# SMART_FARM.net
KiCad netlist of a schematic drawn in Altium Designer
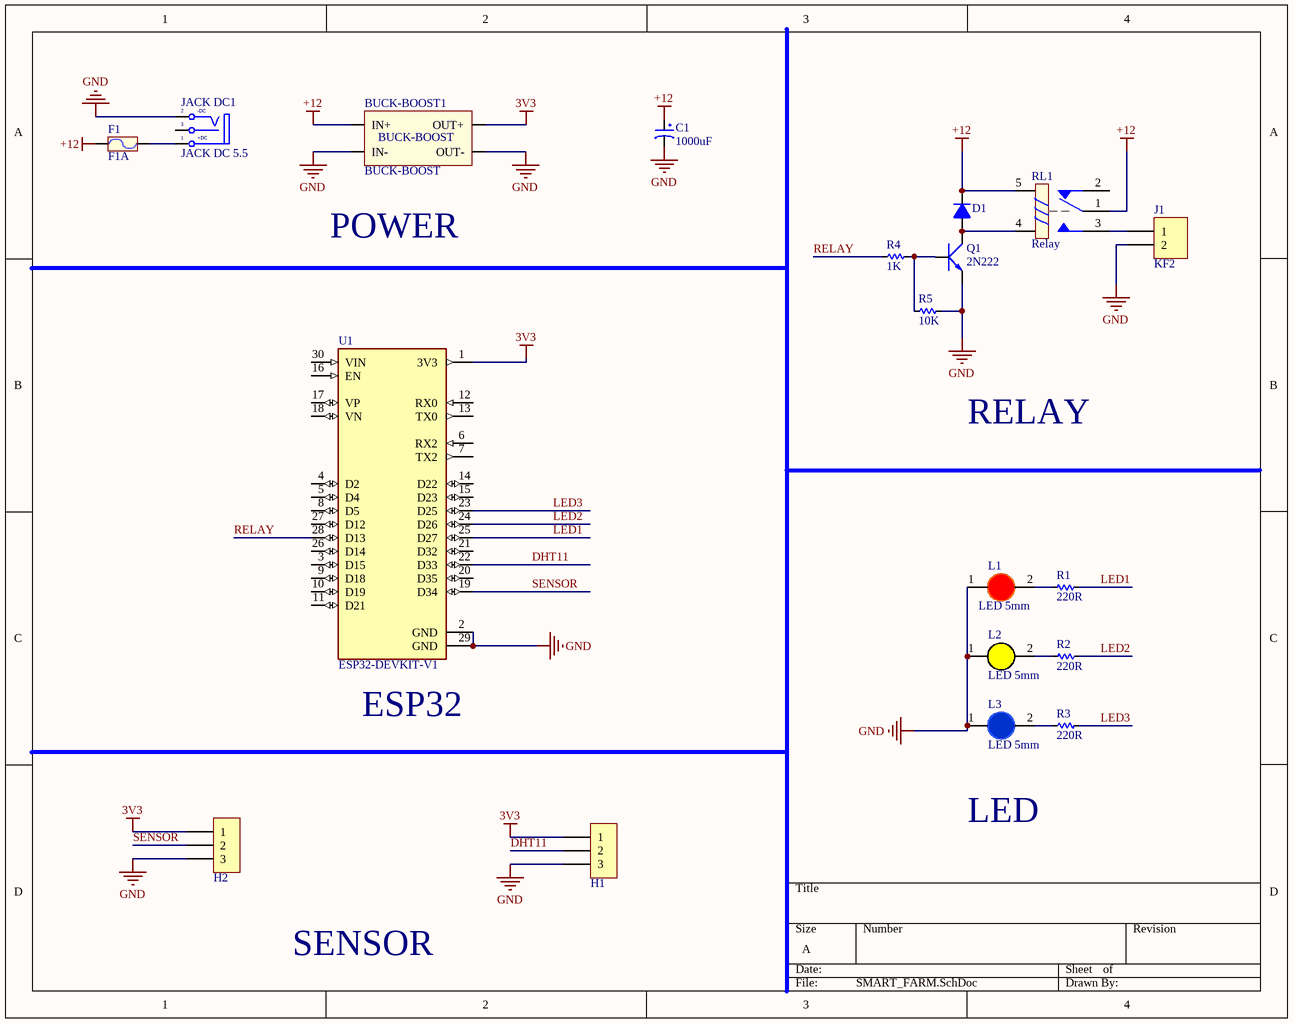
[diagram p0: SMART_FARM.SchDoc]

(export (version "E")
  (design (tool "Eeschema 10.0.6"))
  (components
    (comp (ref "BUCK-BOOST1")
      (value "BUCK-BOOST")
      (footprint "BUCK3A")
      (libsource (lib "Thu Vien Chuan") (part "BUCK-BOOST"))
    )
    (comp (ref "C1")
      (value "1000uF")
      (footprint "tu hoa 13mm")
      (description "Cắm")
      (libsource (lib "Altium_Lib_by_KhueNguyenCreator") (part "Tu Hoa 1000uF 25V 13x21"))
    )
    (comp (ref "D1")
      (value "100v")
      (footprint "DIODE 1A")
      (description "Cắm")
      (libsource (lib "Altium_Lib_by_KhueNguyenCreator") (part "Diode 1N4007"))
    )
    (comp (ref "F1")
      (value "F1A")
      (footprint "FUSE2")
      (description "Fuse")
      (fields (field (name "DESIGNED BY") "VanDungEvn"))
      (libsource (lib "LIBRARY") (part "Fuse"))
    )
    (comp (ref "H1")
      (value "Header 3P 2.54 Duc Thang")
      (footprint "XH2.54M-3")
      (description "Cắm")
      (libsource (lib "Altium_Lib_by_KhueNguyenCreator") (part "Header 3P 2.54 Duc Thang"))
    )
    (comp (ref "H2")
      (value "Header 3P 2.54 Duc Thang")
      (footprint "XH2.54M-3")
      (description "Cắm")
      (libsource (lib "Altium_Lib_by_KhueNguyenCreator") (part "Header 3P 2.54 Duc Thang"))
    )
    (comp (ref "J1")
      (value "KF2")
      (footprint "KF2-5.08")
      (fields
        (field (name "MANUFACTURER") "Würth Elektronik eiSos GmbH")
        (field (name "PARTNO") "691103110002")
        (field (name "CREATED BY") "Karrer Zheng")
      )
      (libsource (lib "Thu Vien Chuan") (part "KF2"))
    )
    (comp (ref "JACK DC1")
      (value "JACK DC 5.5")
      (footprint "JACK DC 5.5")
      (libsource (lib "Altium_Lib_by_KhueNguyenCreator") (part "JACK DC 5.5"))
    )
    (comp (ref "L1")
      (value "LED 5mm")
      (footprint "LED-5MM-RED")
      (description "Cắm")
      (libsource (lib "Altium_Lib_by_KhueNguyenCreator") (part "LED 5mm Do"))
    )
    (comp (ref "L2")
      (value "LED 5mm")
      (footprint "LED-5MM-Yellow")
      (description "Cắm")
      (libsource (lib "Altium_Lib_by_KhueNguyenCreator") (part "LED 5mm Vang"))
    )
    (comp (ref "L3")
      (value "LED 5mm")
      (footprint "LED-5MM-BLUE")
      (description "Cắm")
      (libsource (lib "Altium_Lib_by_KhueNguyenCreator") (part "LED 5mm Xanh Duong"))
    )
    (comp (ref "Q1")
      (value "2N222")
      (footprint "TO92-123")
      (description "NPN 600mW, ECB")
      (libsource (lib "LIBRARY") (part "2N222"))
    )
    (comp (ref "R1")
      (value "220R")
      (footprint "RES-1/4W")
      (description "Res")
      (fields
        (field (name "MANUFACTURER") "Generic Components")
        (field (name "PUBLISHER") "Altium Hobart Technology Centre")
      )
      (libsource (lib "LIBRARY") (part "Res"))
    )
    (comp (ref "R2")
      (value "220R")
      (footprint "RES-1/4W")
      (description "Res")
      (fields
        (field (name "MANUFACTURER") "Generic Components")
        (field (name "PUBLISHER") "Altium Hobart Technology Centre")
      )
      (libsource (lib "LIBRARY") (part "Res"))
    )
    (comp (ref "R3")
      (value "220R")
      (footprint "RES-1/4W")
      (description "Res")
      (fields
        (field (name "MANUFACTURER") "Generic Components")
        (field (name "PUBLISHER") "Altium Hobart Technology Centre")
      )
      (libsource (lib "LIBRARY") (part "Res"))
    )
    (comp (ref "R4")
      (value "1K")
      (footprint "RES-1/4W")
      (description "Res")
      (fields
        (field (name "MANUFACTURER") "Generic Components")
        (field (name "PUBLISHER") "Altium Hobart Technology Centre")
      )
      (libsource (lib "LIBRARY") (part "Res"))
    )
    (comp (ref "R5")
      (value "10K")
      (footprint "RES-1/4W")
      (description "Res")
      (fields
        (field (name "MANUFACTURER") "Generic Components")
        (field (name "PUBLISHER") "Altium Hobart Technology Centre")
      )
      (libsource (lib "LIBRARY") (part "Res"))
    )
    (comp (ref "RL1")
      (value "Relay")
      (footprint "Relay 5 Chan SRD")
      (description "Relay 5 Chan")
      (libsource (lib "Altium_Lib_by_KhueNguyenCreator") (part "Relay 5 Chan SRD"))
    )
    (comp (ref "U1")
      (value "ESP32-DEVKIT-V1")
      (footprint "MODULE_ESP32_DEVKIT_V1")
      (fields (field (name "MF") "Do it"))
      (libsource (lib "ESP32-DEVKIT-V1") (part "ESP32-DEVKIT-V1"))
    )
  )
  (nets
    (net (code "1") (name "+12") (class "Default")
      (node (ref "BUCK-BOOST1") (pin "1") (pinfunction "IN+_1") (pintype "passive"))
      (node (ref "C1") (pin "1") (pinfunction "1_1") (pintype "passive"))
      (node (ref "D1") (pin "2") (pinfunction "K_2") (pintype "passive"))
      (node (ref "F1") (pin "1") (pinfunction "1_1") (pintype "passive"))
      (node (ref "RL1") (pin "1") (pinfunction "1_1") (pintype "passive"))
      (node (ref "RL1") (pin "5") (pinfunction "5_5") (pintype "passive"))
    )
    (net (code "2") (name "/DHT11") (class "Default")
      (node (ref "H1") (pin "2") (pinfunction "2_2") (pintype "passive"))
      (node (ref "U1") (pin "22") (pinfunction "D33_22") (pintype "bidirectional"))
    )
    (net (code "3") (name "/LED1") (class "Default")
      (node (ref "R1") (pin "1") (pinfunction "1_1") (pintype "passive"))
      (node (ref "U1") (pin "25") (pinfunction "D27_25") (pintype "bidirectional"))
    )
    (net (code "4") (name "/LED2") (class "Default")
      (node (ref "R2") (pin "1") (pinfunction "1_1") (pintype "passive"))
      (node (ref "U1") (pin "24") (pinfunction "D26_24") (pintype "bidirectional"))
    )
    (net (code "5") (name "/LED3") (class "Default")
      (node (ref "R3") (pin "1") (pinfunction "1_1") (pintype "passive"))
      (node (ref "U1") (pin "23") (pinfunction "D25_23") (pintype "bidirectional"))
    )
    (net (code "6") (name "/RELAY") (class "Default")
      (node (ref "R4") (pin "2") (pinfunction "2_2") (pintype "passive"))
      (node (ref "U1") (pin "28") (pinfunction "D13_28") (pintype "bidirectional"))
    )
    (net (code "7") (name "/SENSOR") (class "Default")
      (node (ref "H2") (pin "2") (pinfunction "2_2") (pintype "passive"))
      (node (ref "U1") (pin "19") (pinfunction "D34_19") (pintype "bidirectional"))
    )
    (net (code "8") (name "3V3") (class "Default")
      (node (ref "BUCK-BOOST1") (pin "4") (pinfunction "OUT+_4") (pintype "passive"))
      (node (ref "H1") (pin "1") (pinfunction "1_1") (pintype "passive"))
      (node (ref "H2") (pin "1") (pinfunction "1_1") (pintype "passive"))
      (node (ref "U1") (pin "1") (pinfunction "3V3_1") (pintype "output"))
    )
    (net (code "9") (name "GND") (class "Default")
      (node (ref "BUCK-BOOST1") (pin "2") (pinfunction "IN-_2") (pintype "passive"))
      (node (ref "BUCK-BOOST1") (pin "3") (pinfunction "OUT-_3") (pintype "passive"))
      (node (ref "C1") (pin "2") (pinfunction "2_2") (pintype "passive"))
      (node (ref "H1") (pin "3") (pinfunction "3_3") (pintype "passive"))
      (node (ref "H2") (pin "3") (pinfunction "3_3") (pintype "passive"))
      (node (ref "J1") (pin "2") (pinfunction "2_2") (pintype "passive"))
      (node (ref "JACK DC1") (pin "2") (pinfunction "TN_2") (pintype "passive"))
      (node (ref "L1") (pin "1") (pinfunction "A_1") (pintype "passive"))
      (node (ref "L2") (pin "1") (pinfunction "A_1") (pintype "passive"))
      (node (ref "L3") (pin "1") (pinfunction "A_1") (pintype "passive"))
      (node (ref "Q1") (pin "1") (pinfunction "E_1") (pintype "passive"))
      (node (ref "R5") (pin "1") (pinfunction "1_1") (pintype "passive"))
      (node (ref "U1") (pin "2") (pinfunction "GND_2") (pintype "power_in"))
      (node (ref "U1") (pin "29") (pinfunction "GND_29") (pintype "power_in"))
    )
    (net (code "10") (name "Net-(D1-A)") (class "Default")
      (node (ref "D1") (pin "1") (pinfunction "A_1") (pintype "passive"))
      (node (ref "Q1") (pin "3") (pinfunction "C_3") (pintype "passive"))
      (node (ref "RL1") (pin "4") (pinfunction "4_4") (pintype "passive"))
    )
    (net (code "11") (name "Net-(J1-Pad1)") (class "Default")
      (node (ref "J1") (pin "1") (pinfunction "1_1") (pintype "passive"))
      (node (ref "RL1") (pin "3") (pinfunction "3_3") (pintype "passive"))
    )
    (net (code "12") (name "Net-(JACK DC1-T)") (class "Default")
      (node (ref "F1") (pin "2") (pinfunction "2_2") (pintype "passive"))
      (node (ref "JACK DC1") (pin "1") (pinfunction "T_1") (pintype "passive"))
    )
    (net (code "13") (name "Net-(L1-K)") (class "Default")
      (node (ref "L1") (pin "2") (pinfunction "K_2") (pintype "passive"))
      (node (ref "R1") (pin "2") (pinfunction "2_2") (pintype "passive"))
    )
    (net (code "14") (name "Net-(L2-K)") (class "Default")
      (node (ref "L2") (pin "2") (pinfunction "K_2") (pintype "passive"))
      (node (ref "R2") (pin "2") (pinfunction "2_2") (pintype "passive"))
    )
    (net (code "15") (name "Net-(L3-K)") (class "Default")
      (node (ref "L3") (pin "2") (pinfunction "K_2") (pintype "passive"))
      (node (ref "R3") (pin "2") (pinfunction "2_2") (pintype "passive"))
    )
    (net (code "16") (name "Net-(Q1-B)") (class "Default")
      (node (ref "Q1") (pin "2") (pinfunction "B_2") (pintype "passive"))
      (node (ref "R4") (pin "1") (pinfunction "1_1") (pintype "passive"))
      (node (ref "R5") (pin "2") (pinfunction "2_2") (pintype "passive"))
    )
    (net (code "17") (name "unconnected-(JACK DC1-S-Pad3)") (class "Default")
      (node (ref "JACK DC1") (pin "3") (pinfunction "S_3") (pintype "power_in"))
    )
    (net (code "18") (name "unconnected-(RL1-Pad2)") (class "Default")
      (node (ref "RL1") (pin "2") (pinfunction "2_2") (pintype "passive"))
    )
    (net (code "19") (name "unconnected-(U1-D2-Pad4)") (class "Default")
      (node (ref "U1") (pin "4") (pinfunction "D2_4") (pintype "bidirectional"))
    )
    (net (code "20") (name "unconnected-(U1-D4-Pad5)") (class "Default")
      (node (ref "U1") (pin "5") (pinfunction "D4_5") (pintype "bidirectional"))
    )
    (net (code "21") (name "unconnected-(U1-D5-Pad8)") (class "Default")
      (node (ref "U1") (pin "8") (pinfunction "D5_8") (pintype "bidirectional"))
    )
    (net (code "22") (name "unconnected-(U1-D12-Pad27)") (class "Default")
      (node (ref "U1") (pin "27") (pinfunction "D12_27") (pintype "bidirectional"))
    )
    (net (code "23") (name "unconnected-(U1-D14-Pad26)") (class "Default")
      (node (ref "U1") (pin "26") (pinfunction "D14_26") (pintype "bidirectional"))
    )
    (net (code "24") (name "unconnected-(U1-D15-Pad3)") (class "Default")
      (node (ref "U1") (pin "3") (pinfunction "D15_3") (pintype "bidirectional"))
    )
    (net (code "25") (name "unconnected-(U1-D18-Pad9)") (class "Default")
      (node (ref "U1") (pin "9") (pinfunction "D18_9") (pintype "bidirectional"))
    )
    (net (code "26") (name "unconnected-(U1-D19-Pad10)") (class "Default")
      (node (ref "U1") (pin "10") (pinfunction "D19_10") (pintype "bidirectional"))
    )
    (net (code "27") (name "unconnected-(U1-D21-Pad11)") (class "Default")
      (node (ref "U1") (pin "11") (pinfunction "D21_11") (pintype "bidirectional"))
    )
    (net (code "28") (name "unconnected-(U1-D22-Pad14)") (class "Default")
      (node (ref "U1") (pin "14") (pinfunction "D22_14") (pintype "bidirectional"))
    )
    (net (code "29") (name "unconnected-(U1-D23-Pad15)") (class "Default")
      (node (ref "U1") (pin "15") (pinfunction "D23_15") (pintype "bidirectional"))
    )
    (net (code "30") (name "unconnected-(U1-D32-Pad21)") (class "Default")
      (node (ref "U1") (pin "21") (pinfunction "D32_21") (pintype "bidirectional"))
    )
    (net (code "31") (name "unconnected-(U1-D35-Pad20)") (class "Default")
      (node (ref "U1") (pin "20") (pinfunction "D35_20") (pintype "bidirectional"))
    )
    (net (code "32") (name "unconnected-(U1-EN-Pad16)") (class "Default")
      (node (ref "U1") (pin "16") (pinfunction "EN_16") (pintype "input"))
    )
    (net (code "33") (name "unconnected-(U1-RX0-Pad12)") (class "Default")
      (node (ref "U1") (pin "12") (pinfunction "RX0_12") (pintype "input"))
    )
    (net (code "34") (name "unconnected-(U1-RX2-Pad6)") (class "Default")
      (node (ref "U1") (pin "6") (pinfunction "RX2_6") (pintype "input"))
    )
    (net (code "35") (name "unconnected-(U1-TX0-Pad13)") (class "Default")
      (node (ref "U1") (pin "13") (pinfunction "TX0_13") (pintype "output"))
    )
    (net (code "36") (name "unconnected-(U1-TX2-Pad7)") (class "Default")
      (node (ref "U1") (pin "7") (pinfunction "TX2_7") (pintype "output"))
    )
    (net (code "37") (name "unconnected-(U1-VIN-Pad30)") (class "Default")
      (node (ref "U1") (pin "30") (pinfunction "VIN_30") (pintype "input"))
    )
    (net (code "38") (name "unconnected-(U1-VN-Pad18)") (class "Default")
      (node (ref "U1") (pin "18") (pinfunction "VN_18") (pintype "bidirectional"))
    )
    (net (code "39") (name "unconnected-(U1-VP-Pad17)") (class "Default")
      (node (ref "U1") (pin "17") (pinfunction "VP_17") (pintype "bidirectional"))
    )
  )
)
